# DrivePlexer.net
KiCad netlist of a schematic drawn in EAGLE
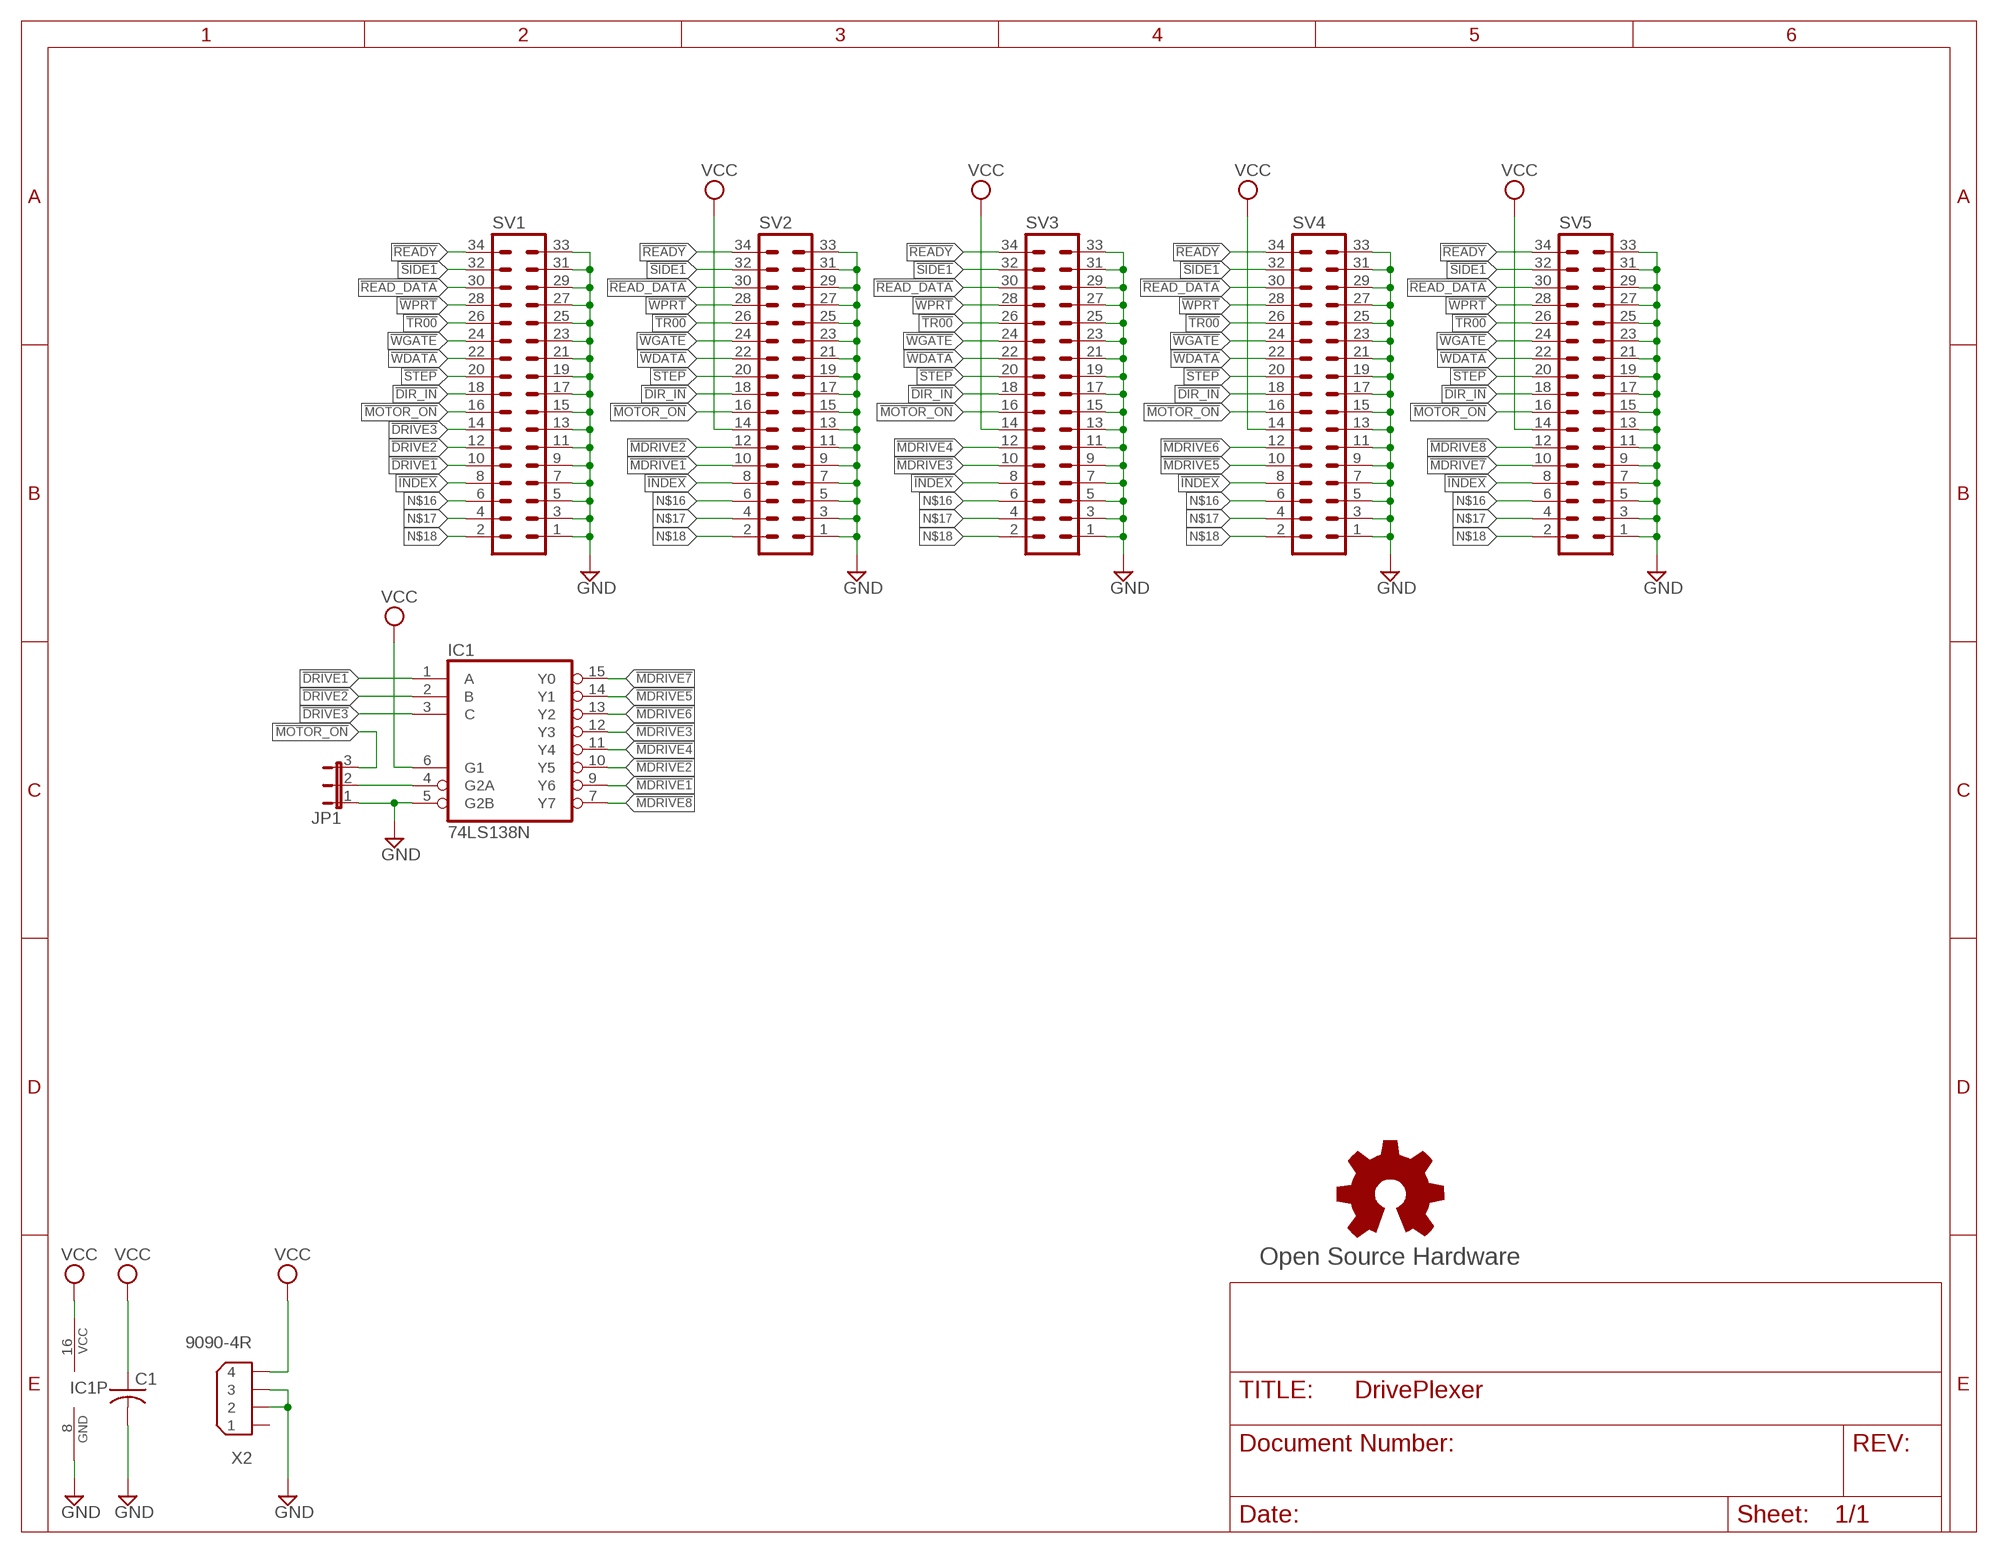
[diagram p0: schematic, sheet 1]

(export (version "E")
  (design (tool "Eeschema 10.0.6"))
  (components
    (comp (ref "C1")
      (value "C-US025-025X050")
      (footprint "eagle-import:C025-025X050")
      (libsource (lib "eagle-import") (part "C-US025-025X050"))
    )
    (comp (ref "GOLD_ORB_SM1")
      (value "Open Source Hardware")
      (footprint "eagle-import:OSHW_5MM")
      (libsource (lib "eagle-import") (part "OSHWLOGOLOGO5MM"))
    )
    (comp (ref "IC1")
      (value "74LS138N")
      (footprint "eagle-import:DIL16-RP")
      (libsource (lib "eagle-import") (part "74138NLS"))
    )
    (comp (ref "JP1")
      (value "JP2E")
      (footprint "eagle-import:JP2")
      (libsource (lib "eagle-import") (part "JP2E"))
    )
    (comp (ref "SV1")
      (value "MA17-2")
      (footprint "eagle-import:MA17-2")
      (libsource (lib "eagle-import") (part "MA17-2"))
    )
    (comp (ref "SV2")
      (value "MA17-2")
      (footprint "eagle-import:MA17-2")
      (libsource (lib "eagle-import") (part "MA17-2"))
    )
    (comp (ref "SV3")
      (value "MA17-2")
      (footprint "eagle-import:MA17-2")
      (libsource (lib "eagle-import") (part "MA17-2"))
    )
    (comp (ref "SV4")
      (value "MA17-2")
      (footprint "eagle-import:MA17-2")
      (libsource (lib "eagle-import") (part "MA17-2"))
    )
    (comp (ref "SV5")
      (value "MA17-2")
      (footprint "eagle-import:MA17-2")
      (libsource (lib "eagle-import") (part "MA17-2"))
    )
    (comp (ref "X2")
      (value "9090-4R")
      (footprint "eagle-import:9090-4R")
      (libsource (lib "eagle-import") (part "9090-4R"))
    )
  )
  (nets
    (net (code "1") (name "/~{DIR_IN}") (class "Default")
      (node (ref "SV1") (pin "18") (pinfunction "18_18") (pintype "passive"))
      (node (ref "SV2") (pin "18") (pinfunction "18_18") (pintype "passive"))
      (node (ref "SV3") (pin "18") (pinfunction "18_18") (pintype "passive"))
      (node (ref "SV4") (pin "18") (pinfunction "18_18") (pintype "passive"))
      (node (ref "SV5") (pin "18") (pinfunction "18_18") (pintype "passive"))
    )
    (net (code "2") (name "/~{DRIVE1}") (class "Default")
      (node (ref "IC1") (pin "1") (pinfunction "A_1") (pintype "input"))
      (node (ref "SV1") (pin "10") (pinfunction "10_10") (pintype "passive"))
    )
    (net (code "3") (name "/~{DRIVE2}") (class "Default")
      (node (ref "IC1") (pin "2") (pinfunction "B_2") (pintype "input"))
      (node (ref "SV1") (pin "12") (pinfunction "12_12") (pintype "passive"))
    )
    (net (code "4") (name "/~{DRIVE3}") (class "Default")
      (node (ref "IC1") (pin "3") (pinfunction "C_3") (pintype "input"))
      (node (ref "SV1") (pin "14") (pinfunction "14_14") (pintype "passive"))
    )
    (net (code "5") (name "/~{INDEX}") (class "Default")
      (node (ref "SV1") (pin "8") (pinfunction "8_8") (pintype "passive"))
      (node (ref "SV2") (pin "8") (pinfunction "8_8") (pintype "passive"))
      (node (ref "SV3") (pin "8") (pinfunction "8_8") (pintype "passive"))
      (node (ref "SV4") (pin "8") (pinfunction "8_8") (pintype "passive"))
      (node (ref "SV5") (pin "8") (pinfunction "8_8") (pintype "passive"))
    )
    (net (code "6") (name "/~{MDRIVE1}") (class "Default")
      (node (ref "IC1") (pin "9") (pinfunction "Y6_9") (pintype "output"))
      (node (ref "SV2") (pin "10") (pinfunction "10_10") (pintype "passive"))
    )
    (net (code "7") (name "/~{MDRIVE2}") (class "Default")
      (node (ref "IC1") (pin "10") (pinfunction "Y5_10") (pintype "output"))
      (node (ref "SV2") (pin "12") (pinfunction "12_12") (pintype "passive"))
    )
    (net (code "8") (name "/~{MDRIVE3}") (class "Default")
      (node (ref "IC1") (pin "12") (pinfunction "Y3_12") (pintype "output"))
      (node (ref "SV3") (pin "10") (pinfunction "10_10") (pintype "passive"))
    )
    (net (code "9") (name "/~{MDRIVE4}") (class "Default")
      (node (ref "IC1") (pin "11") (pinfunction "Y4_11") (pintype "output"))
      (node (ref "SV3") (pin "12") (pinfunction "12_12") (pintype "passive"))
    )
    (net (code "10") (name "/~{MDRIVE5}") (class "Default")
      (node (ref "IC1") (pin "14") (pinfunction "Y1_14") (pintype "output"))
      (node (ref "SV4") (pin "10") (pinfunction "10_10") (pintype "passive"))
    )
    (net (code "11") (name "/~{MDRIVE6}") (class "Default")
      (node (ref "IC1") (pin "13") (pinfunction "Y2_13") (pintype "output"))
      (node (ref "SV4") (pin "12") (pinfunction "12_12") (pintype "passive"))
    )
    (net (code "12") (name "/~{MDRIVE7}") (class "Default")
      (node (ref "IC1") (pin "15") (pinfunction "Y0_15") (pintype "output"))
      (node (ref "SV5") (pin "10") (pinfunction "10_10") (pintype "passive"))
    )
    (net (code "13") (name "/~{MDRIVE8}") (class "Default")
      (node (ref "IC1") (pin "7") (pinfunction "Y7_7") (pintype "output"))
      (node (ref "SV5") (pin "12") (pinfunction "12_12") (pintype "passive"))
    )
    (net (code "14") (name "/~{MOTOR_ON}") (class "Default")
      (node (ref "JP1") (pin "3") (pinfunction "3_3") (pintype "passive"))
      (node (ref "SV1") (pin "16") (pinfunction "16_16") (pintype "passive"))
      (node (ref "SV2") (pin "16") (pinfunction "16_16") (pintype "passive"))
      (node (ref "SV3") (pin "16") (pinfunction "16_16") (pintype "passive"))
      (node (ref "SV4") (pin "16") (pinfunction "16_16") (pintype "passive"))
      (node (ref "SV5") (pin "16") (pinfunction "16_16") (pintype "passive"))
    )
    (net (code "15") (name "/~{READY}") (class "Default")
      (node (ref "SV1") (pin "34") (pinfunction "34_34") (pintype "passive"))
      (node (ref "SV2") (pin "34") (pinfunction "34_34") (pintype "passive"))
      (node (ref "SV3") (pin "34") (pinfunction "34_34") (pintype "passive"))
      (node (ref "SV4") (pin "34") (pinfunction "34_34") (pintype "passive"))
      (node (ref "SV5") (pin "34") (pinfunction "34_34") (pintype "passive"))
    )
    (net (code "16") (name "/~{READ_DATA}") (class "Default")
      (node (ref "SV1") (pin "30") (pinfunction "30_30") (pintype "passive"))
      (node (ref "SV2") (pin "30") (pinfunction "30_30") (pintype "passive"))
      (node (ref "SV3") (pin "30") (pinfunction "30_30") (pintype "passive"))
      (node (ref "SV4") (pin "30") (pinfunction "30_30") (pintype "passive"))
      (node (ref "SV5") (pin "30") (pinfunction "30_30") (pintype "passive"))
    )
    (net (code "17") (name "/~{SIDE1}") (class "Default")
      (node (ref "SV1") (pin "32") (pinfunction "32_32") (pintype "passive"))
      (node (ref "SV2") (pin "32") (pinfunction "32_32") (pintype "passive"))
      (node (ref "SV3") (pin "32") (pinfunction "32_32") (pintype "passive"))
      (node (ref "SV4") (pin "32") (pinfunction "32_32") (pintype "passive"))
      (node (ref "SV5") (pin "32") (pinfunction "32_32") (pintype "passive"))
    )
    (net (code "18") (name "/~{STEP}") (class "Default")
      (node (ref "SV1") (pin "20") (pinfunction "20_20") (pintype "passive"))
      (node (ref "SV2") (pin "20") (pinfunction "20_20") (pintype "passive"))
      (node (ref "SV3") (pin "20") (pinfunction "20_20") (pintype "passive"))
      (node (ref "SV4") (pin "20") (pinfunction "20_20") (pintype "passive"))
      (node (ref "SV5") (pin "20") (pinfunction "20_20") (pintype "passive"))
    )
    (net (code "19") (name "/~{TR00}") (class "Default")
      (node (ref "SV1") (pin "26") (pinfunction "26_26") (pintype "passive"))
      (node (ref "SV2") (pin "26") (pinfunction "26_26") (pintype "passive"))
      (node (ref "SV3") (pin "26") (pinfunction "26_26") (pintype "passive"))
      (node (ref "SV4") (pin "26") (pinfunction "26_26") (pintype "passive"))
      (node (ref "SV5") (pin "26") (pinfunction "26_26") (pintype "passive"))
    )
    (net (code "20") (name "/~{WDATA}") (class "Default")
      (node (ref "SV1") (pin "22") (pinfunction "22_22") (pintype "passive"))
      (node (ref "SV2") (pin "22") (pinfunction "22_22") (pintype "passive"))
      (node (ref "SV3") (pin "22") (pinfunction "22_22") (pintype "passive"))
      (node (ref "SV4") (pin "22") (pinfunction "22_22") (pintype "passive"))
      (node (ref "SV5") (pin "22") (pinfunction "22_22") (pintype "passive"))
    )
    (net (code "21") (name "/~{WGATE}") (class "Default")
      (node (ref "SV1") (pin "24") (pinfunction "24_24") (pintype "passive"))
      (node (ref "SV2") (pin "24") (pinfunction "24_24") (pintype "passive"))
      (node (ref "SV3") (pin "24") (pinfunction "24_24") (pintype "passive"))
      (node (ref "SV4") (pin "24") (pinfunction "24_24") (pintype "passive"))
      (node (ref "SV5") (pin "24") (pinfunction "24_24") (pintype "passive"))
    )
    (net (code "22") (name "/~{WPRT}") (class "Default")
      (node (ref "SV1") (pin "28") (pinfunction "28_28") (pintype "passive"))
      (node (ref "SV2") (pin "28") (pinfunction "28_28") (pintype "passive"))
      (node (ref "SV3") (pin "28") (pinfunction "28_28") (pintype "passive"))
      (node (ref "SV4") (pin "28") (pinfunction "28_28") (pintype "passive"))
      (node (ref "SV5") (pin "28") (pinfunction "28_28") (pintype "passive"))
    )
    (net (code "23") (name "GND") (class "Default")
      (node (ref "C1") (pin "2") (pinfunction "2_2") (pintype "passive"))
      (node (ref "IC1") (pin "5") (pinfunction "G2B_5") (pintype "input"))
      (node (ref "IC1") (pin "8") (pinfunction "GND_8") (pintype "power_in"))
      (node (ref "JP1") (pin "1") (pinfunction "1_1") (pintype "passive"))
      (node (ref "SV1") (pin "1") (pinfunction "1_1") (pintype "passive"))
      (node (ref "SV1") (pin "11") (pinfunction "11_11") (pintype "passive"))
      (node (ref "SV1") (pin "13") (pinfunction "13_13") (pintype "passive"))
      (node (ref "SV1") (pin "15") (pinfunction "15_15") (pintype "passive"))
      (node (ref "SV1") (pin "17") (pinfunction "17_17") (pintype "passive"))
      (node (ref "SV1") (pin "19") (pinfunction "19_19") (pintype "passive"))
      (node (ref "SV1") (pin "21") (pinfunction "21_21") (pintype "passive"))
      (node (ref "SV1") (pin "23") (pinfunction "23_23") (pintype "passive"))
      (node (ref "SV1") (pin "25") (pinfunction "25_25") (pintype "passive"))
      (node (ref "SV1") (pin "27") (pinfunction "27_27") (pintype "passive"))
      (node (ref "SV1") (pin "29") (pinfunction "29_29") (pintype "passive"))
      (node (ref "SV1") (pin "3") (pinfunction "3_3") (pintype "passive"))
      (node (ref "SV1") (pin "31") (pinfunction "31_31") (pintype "passive"))
      (node (ref "SV1") (pin "33") (pinfunction "33_33") (pintype "passive"))
      (node (ref "SV1") (pin "5") (pinfunction "5_5") (pintype "passive"))
      (node (ref "SV1") (pin "7") (pinfunction "7_7") (pintype "passive"))
      (node (ref "SV1") (pin "9") (pinfunction "9_9") (pintype "passive"))
      (node (ref "SV2") (pin "1") (pinfunction "1_1") (pintype "passive"))
      (node (ref "SV2") (pin "11") (pinfunction "11_11") (pintype "passive"))
      (node (ref "SV2") (pin "13") (pinfunction "13_13") (pintype "passive"))
      (node (ref "SV2") (pin "15") (pinfunction "15_15") (pintype "passive"))
      (node (ref "SV2") (pin "17") (pinfunction "17_17") (pintype "passive"))
      (node (ref "SV2") (pin "19") (pinfunction "19_19") (pintype "passive"))
      (node (ref "SV2") (pin "21") (pinfunction "21_21") (pintype "passive"))
      (node (ref "SV2") (pin "23") (pinfunction "23_23") (pintype "passive"))
      (node (ref "SV2") (pin "25") (pinfunction "25_25") (pintype "passive"))
      (node (ref "SV2") (pin "27") (pinfunction "27_27") (pintype "passive"))
      (node (ref "SV2") (pin "29") (pinfunction "29_29") (pintype "passive"))
      (node (ref "SV2") (pin "3") (pinfunction "3_3") (pintype "passive"))
      (node (ref "SV2") (pin "31") (pinfunction "31_31") (pintype "passive"))
      (node (ref "SV2") (pin "33") (pinfunction "33_33") (pintype "passive"))
      (node (ref "SV2") (pin "5") (pinfunction "5_5") (pintype "passive"))
      (node (ref "SV2") (pin "7") (pinfunction "7_7") (pintype "passive"))
      (node (ref "SV2") (pin "9") (pinfunction "9_9") (pintype "passive"))
      (node (ref "SV3") (pin "1") (pinfunction "1_1") (pintype "passive"))
      (node (ref "SV3") (pin "11") (pinfunction "11_11") (pintype "passive"))
      (node (ref "SV3") (pin "13") (pinfunction "13_13") (pintype "passive"))
      (node (ref "SV3") (pin "15") (pinfunction "15_15") (pintype "passive"))
      (node (ref "SV3") (pin "17") (pinfunction "17_17") (pintype "passive"))
      (node (ref "SV3") (pin "19") (pinfunction "19_19") (pintype "passive"))
      (node (ref "SV3") (pin "21") (pinfunction "21_21") (pintype "passive"))
      (node (ref "SV3") (pin "23") (pinfunction "23_23") (pintype "passive"))
      (node (ref "SV3") (pin "25") (pinfunction "25_25") (pintype "passive"))
      (node (ref "SV3") (pin "27") (pinfunction "27_27") (pintype "passive"))
      (node (ref "SV3") (pin "29") (pinfunction "29_29") (pintype "passive"))
      (node (ref "SV3") (pin "3") (pinfunction "3_3") (pintype "passive"))
      (node (ref "SV3") (pin "31") (pinfunction "31_31") (pintype "passive"))
      (node (ref "SV3") (pin "33") (pinfunction "33_33") (pintype "passive"))
      (node (ref "SV3") (pin "5") (pinfunction "5_5") (pintype "passive"))
      (node (ref "SV3") (pin "7") (pinfunction "7_7") (pintype "passive"))
      (node (ref "SV3") (pin "9") (pinfunction "9_9") (pintype "passive"))
      (node (ref "SV4") (pin "1") (pinfunction "1_1") (pintype "passive"))
      (node (ref "SV4") (pin "11") (pinfunction "11_11") (pintype "passive"))
      (node (ref "SV4") (pin "13") (pinfunction "13_13") (pintype "passive"))
      (node (ref "SV4") (pin "15") (pinfunction "15_15") (pintype "passive"))
      (node (ref "SV4") (pin "17") (pinfunction "17_17") (pintype "passive"))
      (node (ref "SV4") (pin "19") (pinfunction "19_19") (pintype "passive"))
      (node (ref "SV4") (pin "21") (pinfunction "21_21") (pintype "passive"))
      (node (ref "SV4") (pin "23") (pinfunction "23_23") (pintype "passive"))
      (node (ref "SV4") (pin "25") (pinfunction "25_25") (pintype "passive"))
      (node (ref "SV4") (pin "27") (pinfunction "27_27") (pintype "passive"))
      (node (ref "SV4") (pin "29") (pinfunction "29_29") (pintype "passive"))
      (node (ref "SV4") (pin "3") (pinfunction "3_3") (pintype "passive"))
      (node (ref "SV4") (pin "31") (pinfunction "31_31") (pintype "passive"))
      (node (ref "SV4") (pin "33") (pinfunction "33_33") (pintype "passive"))
      (node (ref "SV4") (pin "5") (pinfunction "5_5") (pintype "passive"))
      (node (ref "SV4") (pin "7") (pinfunction "7_7") (pintype "passive"))
      (node (ref "SV4") (pin "9") (pinfunction "9_9") (pintype "passive"))
      (node (ref "SV5") (pin "1") (pinfunction "1_1") (pintype "passive"))
      (node (ref "SV5") (pin "11") (pinfunction "11_11") (pintype "passive"))
      (node (ref "SV5") (pin "13") (pinfunction "13_13") (pintype "passive"))
      (node (ref "SV5") (pin "15") (pinfunction "15_15") (pintype "passive"))
      (node (ref "SV5") (pin "17") (pinfunction "17_17") (pintype "passive"))
      (node (ref "SV5") (pin "19") (pinfunction "19_19") (pintype "passive"))
      (node (ref "SV5") (pin "21") (pinfunction "21_21") (pintype "passive"))
      (node (ref "SV5") (pin "23") (pinfunction "23_23") (pintype "passive"))
      (node (ref "SV5") (pin "25") (pinfunction "25_25") (pintype "passive"))
      (node (ref "SV5") (pin "27") (pinfunction "27_27") (pintype "passive"))
      (node (ref "SV5") (pin "29") (pinfunction "29_29") (pintype "passive"))
      (node (ref "SV5") (pin "3") (pinfunction "3_3") (pintype "passive"))
      (node (ref "SV5") (pin "31") (pinfunction "31_31") (pintype "passive"))
      (node (ref "SV5") (pin "33") (pinfunction "33_33") (pintype "passive"))
      (node (ref "SV5") (pin "5") (pinfunction "5_5") (pintype "passive"))
      (node (ref "SV5") (pin "7") (pinfunction "7_7") (pintype "passive"))
      (node (ref "SV5") (pin "9") (pinfunction "9_9") (pintype "passive"))
      (node (ref "X2") (pin "2") (pinfunction "2_2") (pintype "passive"))
      (node (ref "X2") (pin "3") (pinfunction "3_3") (pintype "passive"))
    )
    (net (code "24") (name "N$16") (class "Default")
      (node (ref "SV1") (pin "6") (pinfunction "6_6") (pintype "passive"))
      (node (ref "SV2") (pin "6") (pinfunction "6_6") (pintype "passive"))
      (node (ref "SV3") (pin "6") (pinfunction "6_6") (pintype "passive"))
      (node (ref "SV4") (pin "6") (pinfunction "6_6") (pintype "passive"))
      (node (ref "SV5") (pin "6") (pinfunction "6_6") (pintype "passive"))
    )
    (net (code "25") (name "N$17") (class "Default")
      (node (ref "SV1") (pin "4") (pinfunction "4_4") (pintype "passive"))
      (node (ref "SV2") (pin "4") (pinfunction "4_4") (pintype "passive"))
      (node (ref "SV3") (pin "4") (pinfunction "4_4") (pintype "passive"))
      (node (ref "SV4") (pin "4") (pinfunction "4_4") (pintype "passive"))
      (node (ref "SV5") (pin "4") (pinfunction "4_4") (pintype "passive"))
    )
    (net (code "26") (name "N$18") (class "Default")
      (node (ref "SV1") (pin "2") (pinfunction "2_2") (pintype "passive"))
      (node (ref "SV2") (pin "2") (pinfunction "2_2") (pintype "passive"))
      (node (ref "SV3") (pin "2") (pinfunction "2_2") (pintype "passive"))
      (node (ref "SV4") (pin "2") (pinfunction "2_2") (pintype "passive"))
      (node (ref "SV5") (pin "2") (pinfunction "2_2") (pintype "passive"))
    )
    (net (code "27") (name "Net-(IC1A-G2A)") (class "Default")
      (node (ref "IC1") (pin "4") (pinfunction "G2A_4") (pintype "input"))
      (node (ref "JP1") (pin "2") (pinfunction "2_2") (pintype "passive"))
    )
    (net (code "28") (name "VCC") (class "Default")
      (node (ref "C1") (pin "1") (pinfunction "1_1") (pintype "passive"))
      (node (ref "IC1") (pin "16") (pinfunction "VCC_16") (pintype "power_in"))
      (node (ref "IC1") (pin "6") (pinfunction "G1_6") (pintype "input"))
      (node (ref "SV2") (pin "14") (pinfunction "14_14") (pintype "passive"))
      (node (ref "SV3") (pin "14") (pinfunction "14_14") (pintype "passive"))
      (node (ref "SV4") (pin "14") (pinfunction "14_14") (pintype "passive"))
      (node (ref "SV5") (pin "14") (pinfunction "14_14") (pintype "passive"))
      (node (ref "X2") (pin "4") (pinfunction "4_4") (pintype "passive"))
    )
    (net (code "29") (name "unconnected-(X2-Pad1)") (class "Default")
      (node (ref "X2") (pin "1") (pinfunction "1_1") (pintype "passive"))
    )
  )
)
